# 103RCT6CORE.net
KiCad netlist of a schematic drawn in Altium Designer
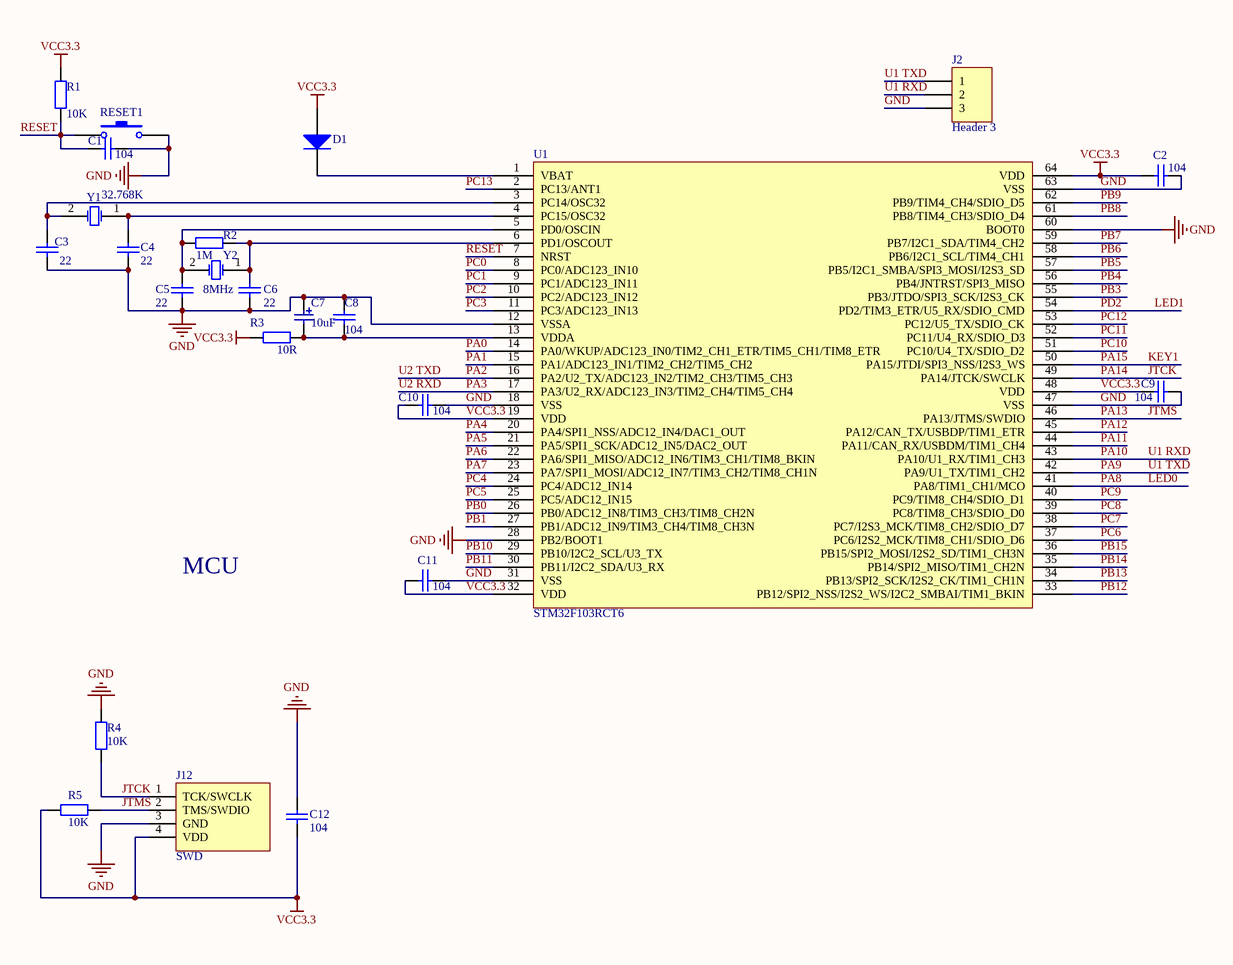
[diagram p0: 103RCT6CORE.SchDoc]

(export (version "E")
  (design (tool "Eeschema 10.0.6"))
  (components
    (comp (ref "C1")
      (value "104")
      (footprint "0805C")
      (description "Capacitor")
      (fields (field (name "Comment") "Cap") (field (name "PUBLISHER") "Altium Limited"))
      (libsource (lib "Miscellaneous Devices") (part "Cap"))
    )
    (comp (ref "C2")
      (value "104")
      (footprint "0805C")
      (description "Capacitor")
      (fields (field (name "Comment") "Cap") (field (name "PUBLISHER") "Altium Limited"))
      (libsource (lib "Miscellaneous Devices") (part "Cap"))
    )
    (comp (ref "C3")
      (value "22")
      (footprint "0805C")
      (description "Capacitor")
      (fields (field (name "Comment") "Cap") (field (name "PUBLISHER") "Altium Limited"))
      (libsource (lib "Miscellaneous Devices") (part "Cap"))
    )
    (comp (ref "C4")
      (value "22")
      (footprint "0805C")
      (description "Capacitor")
      (fields (field (name "Comment") "Cap") (field (name "PUBLISHER") "Altium Limited"))
      (libsource (lib "Miscellaneous Devices") (part "Cap"))
    )
    (comp (ref "C5")
      (value "22")
      (footprint "0805C")
      (description "Capacitor")
      (fields (field (name "Comment") "Cap") (field (name "PUBLISHER") "Altium Limited"))
      (libsource (lib "Miscellaneous Devices") (part "Cap"))
    )
    (comp (ref "C6")
      (value "22")
      (footprint "0805C")
      (description "Capacitor")
      (fields (field (name "Comment") "Cap") (field (name "PUBLISHER") "Altium Limited"))
      (libsource (lib "Miscellaneous Devices") (part "Cap"))
    )
    (comp (ref "C7") (value "10uF") (footprint "3216T") (libsource (lib "basic") (part "CAP-POL1")))
    (comp (ref "C8")
      (value "104")
      (footprint "0805c")
      (description "Capacitor")
      (fields (field (name "Comment") "Cap") (field (name "PUBLISHER") "Altium Limited"))
      (libsource (lib "Miscellaneous Devices") (part "Cap"))
    )
    (comp (ref "C9")
      (value "104")
      (footprint "0805C")
      (description "Capacitor")
      (fields (field (name "Comment") "Cap") (field (name "PUBLISHER") "Altium Limited"))
      (libsource (lib "Miscellaneous Devices") (part "Cap"))
    )
    (comp (ref "C10")
      (value "104")
      (footprint "0805C")
      (description "Capacitor")
      (fields (field (name "Comment") "Cap") (field (name "PUBLISHER") "Altium Limited"))
      (libsource (lib "Miscellaneous Devices") (part "Cap"))
    )
    (comp (ref "C11")
      (value "104")
      (footprint "0805C")
      (description "Capacitor")
      (fields (field (name "Comment") "Cap") (field (name "PUBLISHER") "Altium Limited"))
      (libsource (lib "Miscellaneous Devices") (part "Cap"))
    )
    (comp (ref "C12")
      (value "104")
      (footprint "0805C")
      (description "Capacitor")
      (fields (field (name "Comment") "Cap") (field (name "PUBLISHER") "Altium Limited"))
      (libsource (lib "Miscellaneous Devices") (part "Cap"))
    )
    (comp (ref "D1")
      (value "Diode 1N914")
      (footprint "1206")
      (description "High Conductance Fast Diode")
      (fields (field (name "PUBLISHER") "Altium Limited"))
      (libsource (lib "Miscellaneous Devices") (part "Diode 1N914"))
    )
    (comp (ref "J2")
      (value "Header 3")
      (footprint "HDR1X3")
      (description "Header, 3-Pin")
      (fields (field (name "PUBLISHER") "Altium Limited"))
      (libsource (lib "Miscellaneous Connectors") (part "Header 3"))
    )
    (comp (ref "J12") (value "SWD") (footprint "SWD") (libsource (lib "STM32") (part "SWD")))
    (comp (ref "R1")
      (value "10K")
      (footprint "0805")
      (description "Resistor")
      (fields (field (name "Comment") "Res2") (field (name "PUBLISHER") "Altium Limited"))
      (libsource (lib "") (part "Res2_2"))
    )
    (comp (ref "R2")
      (value "1M")
      (footprint "0805")
      (description "Resistor")
      (fields (field (name "Comment") "Res2") (field (name "PUBLISHER") "Altium Limited"))
      (libsource (lib "Miscellaneous Devices") (part "Res2"))
    )
    (comp (ref "R3")
      (value "10R")
      (footprint "0805")
      (description "Resistor")
      (fields (field (name "Comment") "Res2") (field (name "PUBLISHER") "Altium Limited"))
      (libsource (lib "Miscellaneous Devices") (part "Res2"))
    )
    (comp (ref "R4")
      (value "10K")
      (footprint "0805")
      (description "Resistor")
      (fields (field (name "Comment") "Res2") (field (name "PUBLISHER") "Altium Limited"))
      (libsource (lib "") (part "Res2_1"))
    )
    (comp (ref "R5")
      (value "10K")
      (footprint "0805")
      (description "Resistor")
      (fields (field (name "Comment") "Res2") (field (name "PUBLISHER") "Altium Limited"))
      (libsource (lib "Miscellaneous Devices") (part "Res2"))
    )
    (comp (ref "RESET1")
      (value "SW-PB")
      (footprint "SWITCH")
      (description "Switch")
      (fields (field (name "PUBLISHER") "Altium Limited"))
      (libsource (lib "Miscellaneous Devices") (part "SW-PB"))
    )
    (comp (ref "U1")
      (value "STM32F103RCT6")
      (footprint "STM32F103RCT6")
      (libsource (lib "Schlib1") (part "STM32F103RCT6"))
    )
    (comp (ref "Y1")
      (value "XTAL")
      (footprint "tc-26")
      (description "Crystal Oscillator")
      (fields (field (name "PUBLISHER") "Altium Limited"))
      (libsource (lib "Miscellaneous Devices") (part "XTAL"))
    )
    (comp (ref "Y2")
      (value "8MHz")
      (footprint "Y2")
      (description "Crystal Oscillator")
      (fields (field (name "PUBLISHER") "Altium Limited"))
      (libsource (lib "Miscellaneous Devices") (part "XTAL"))
    )
  )
  (nets
    (net (code "1") (name "/32.768K") (class "Default")
      (node (ref "C3") (pin "2") (pinfunction "2_2") (pintype "passive"))
      (node (ref "U1") (pin "3") (pinfunction "PC14/OSC32_3") (pintype "passive"))
      (node (ref "Y1") (pin "2") (pinfunction "OSC2_2") (pintype "passive"))
    )
    (net (code "2") (name "/JTCK") (class "Default")
      (node (ref "J12") (pin "1") (pinfunction "TCK/SWCLK_1") (pintype "passive"))
      (node (ref "R4") (pin "2") (pinfunction "2_2") (pintype "passive"))
      (node (ref "U1") (pin "49") (pinfunction "PA14/JTCK/SWCLK_49") (pintype "passive"))
    )
    (net (code "3") (name "/JTMS") (class "Default")
      (node (ref "J12") (pin "2") (pinfunction "TMS/SWDIO_2") (pintype "passive"))
      (node (ref "R5") (pin "1") (pinfunction "1_1") (pintype "passive"))
      (node (ref "U1") (pin "46") (pinfunction "PA13/JTMS/SWDIO_46") (pintype "passive"))
    )
    (net (code "4") (name "/KEY1") (class "Default")
      (node (ref "U1") (pin "50") (pinfunction "PA15/JTDI/SPI3_NSS/I2S3_WS_50") (pintype "passive"))
    )
    (net (code "5") (name "/LED0") (class "Default")
      (node (ref "U1") (pin "41") (pinfunction "PA8/TIM1_CH1/MCO_41") (pintype "passive"))
    )
    (net (code "6") (name "/LED1") (class "Default")
      (node (ref "U1") (pin "54") (pinfunction "PD2/TIM3_ETR/U5_RX/SDIO_CMD_54") (pintype "passive"))
    )
    (net (code "8") (name "/PA0") (class "Default")
      (node (ref "U1") (pin "14") (pinfunction "PA0/WKUP/ADC123_IN0/TIM2_CH1_ETR/TIM5_CH1/TIM8_ETR_14") (pintype "passive"))
    )
    (net (code "9") (name "/PA1") (class "Default")
      (node (ref "U1") (pin "15") (pinfunction "PA1/ADC123_IN1/TIM2_CH2/TIM5_CH2_15") (pintype "passive"))
    )
    (net (code "10") (name "/PA2") (class "Default")
      (node (ref "U1") (pin "16") (pinfunction "PA2/U2_TX/ADC123_IN2/TIM2_CH3/TIM5_CH3_16") (pintype "passive"))
    )
    (net (code "11") (name "/PA3") (class "Default")
      (node (ref "U1") (pin "17") (pinfunction "PA3/U2_RX/ADC123_IN3/TIM2_CH4/TIM5_CH4_17") (pintype "passive"))
    )
    (net (code "12") (name "/PA4") (class "Default")
      (node (ref "U1") (pin "20") (pinfunction "PA4/SPI1_NSS/ADC12_IN4/DAC1_OUT_20") (pintype "passive"))
    )
    (net (code "13") (name "/PA5") (class "Default")
      (node (ref "U1") (pin "21") (pinfunction "PA5/SPI1_SCK/ADC12_IN5/DAC2_OUT_21") (pintype "passive"))
    )
    (net (code "14") (name "/PA6") (class "Default")
      (node (ref "U1") (pin "22") (pinfunction "PA6/SPI1_MISO/ADC12_IN6/TIM3_CH1/TIM8_BKIN_22") (pintype "passive"))
    )
    (net (code "15") (name "/PA7") (class "Default")
      (node (ref "U1") (pin "23") (pinfunction "PA7/SPI1_MOSI/ADC12_IN7/TIM3_CH2/TIM8_CH1N_23") (pintype "passive"))
    )
    (net (code "16") (name "/PA9") (class "Default")
      (node (ref "J2") (pin "1") (pinfunction "1_1") (pintype "passive"))
      (node (ref "U1") (pin "42") (pinfunction "PA9/U1_TX/TIM1_CH2_42") (pintype "passive"))
    )
    (net (code "17") (name "/PA10") (class "Default")
      (node (ref "J2") (pin "2") (pinfunction "2_2") (pintype "passive"))
      (node (ref "U1") (pin "43") (pinfunction "PA10/U1_RX/TIM1_CH3_43") (pintype "passive"))
    )
    (net (code "18") (name "/PA11") (class "Default")
      (node (ref "U1") (pin "44") (pinfunction "PA11/CAN_RX/USBDM/TIM1_CH4_44") (pintype "passive"))
    )
    (net (code "19") (name "/PA12") (class "Default")
      (node (ref "U1") (pin "45") (pinfunction "PA12/CAN_TX/USBDP/TIM1_ETR_45") (pintype "passive"))
    )
    (net (code "20") (name "/PB0") (class "Default")
      (node (ref "U1") (pin "26") (pinfunction "PB0/ADC12_IN8/TIM3_CH3/TIM8_CH2N_26") (pintype "passive"))
    )
    (net (code "21") (name "/PB1") (class "Default")
      (node (ref "U1") (pin "27") (pinfunction "PB1/ADC12_IN9/TIM3_CH4/TIM8_CH3N_27") (pintype "passive"))
    )
    (net (code "22") (name "/PB3") (class "Default")
      (node (ref "U1") (pin "55") (pinfunction "PB3/JTDO/SPI3_SCK/I2S3_CK_55") (pintype "passive"))
    )
    (net (code "23") (name "/PB4") (class "Default")
      (node (ref "U1") (pin "56") (pinfunction "PB4/JNTRST/SPI3_MISO_56") (pintype "passive"))
    )
    (net (code "24") (name "/PB5") (class "Default")
      (node (ref "U1") (pin "57") (pinfunction "PB5/I2C1_SMBA/SPI3_MOSI/I2S3_SD_57") (pintype "passive"))
    )
    (net (code "25") (name "/PB6") (class "Default")
      (node (ref "U1") (pin "58") (pinfunction "PB6/I2C1_SCL/TIM4_CH1_58") (pintype "passive"))
    )
    (net (code "26") (name "/PB7") (class "Default")
      (node (ref "U1") (pin "59") (pinfunction "PB7/I2C1_SDA/TIM4_CH2_59") (pintype "passive"))
    )
    (net (code "27") (name "/PB8") (class "Default")
      (node (ref "U1") (pin "61") (pinfunction "PB8/TIM4_CH3/SDIO_D4_61") (pintype "passive"))
    )
    (net (code "28") (name "/PB9") (class "Default")
      (node (ref "U1") (pin "62") (pinfunction "PB9/TIM4_CH4/SDIO_D5_62") (pintype "passive"))
    )
    (net (code "29") (name "/PB10") (class "Default")
      (node (ref "U1") (pin "29") (pinfunction "PB10/I2C2_SCL/U3_TX_29") (pintype "passive"))
    )
    (net (code "30") (name "/PB11") (class "Default")
      (node (ref "U1") (pin "30") (pinfunction "PB11/I2C2_SDA/U3_RX_30") (pintype "passive"))
    )
    (net (code "31") (name "/PB12") (class "Default")
      (node (ref "U1") (pin "33") (pinfunction "PB12/SPI2_NSS/I2S2_WS/I2C2_SMBAI/TIM1_BKIN_33") (pintype "passive"))
    )
    (net (code "32") (name "/PB13") (class "Default")
      (node (ref "U1") (pin "34") (pinfunction "PB13/SPI2_SCK/I2S2_CK/TIM1_CH1N_34") (pintype "passive"))
    )
    (net (code "33") (name "/PB14") (class "Default")
      (node (ref "U1") (pin "35") (pinfunction "PB14/SPI2_MISO/TIM1_CH2N_35") (pintype "passive"))
    )
    (net (code "34") (name "/PB15") (class "Default")
      (node (ref "U1") (pin "36") (pinfunction "PB15/SPI2_MOSI/I2S2_SD/TIM1_CH3N_36") (pintype "passive"))
    )
    (net (code "35") (name "/PC0") (class "Default")
      (node (ref "U1") (pin "8") (pinfunction "PC0/ADC123_IN10_8") (pintype "passive"))
    )
    (net (code "36") (name "/PC1") (class "Default")
      (node (ref "U1") (pin "9") (pinfunction "PC1/ADC123_IN11_9") (pintype "passive"))
    )
    (net (code "37") (name "/PC2") (class "Default")
      (node (ref "U1") (pin "10") (pinfunction "PC2/ADC123_IN12_10") (pintype "passive"))
    )
    (net (code "38") (name "/PC3") (class "Default")
      (node (ref "U1") (pin "11") (pinfunction "PC3/ADC123_IN13_11") (pintype "passive"))
    )
    (net (code "39") (name "/PC4") (class "Default")
      (node (ref "U1") (pin "24") (pinfunction "PC4/ADC12_IN14_24") (pintype "passive"))
    )
    (net (code "40") (name "/PC5") (class "Default")
      (node (ref "U1") (pin "25") (pinfunction "PC5/ADC12_IN15_25") (pintype "passive"))
    )
    (net (code "41") (name "/PC6") (class "Default")
      (node (ref "U1") (pin "37") (pinfunction "PC6/I2S2_MCK/TIM8_CH1/SDIO_D6_37") (pintype "passive"))
    )
    (net (code "42") (name "/PC7") (class "Default")
      (node (ref "U1") (pin "38") (pinfunction "PC7/I2S3_MCK/TIM8_CH2/SDIO_D7_38") (pintype "passive"))
    )
    (net (code "43") (name "/PC8") (class "Default")
      (node (ref "U1") (pin "39") (pinfunction "PC8/TIM8_CH3/SDIO_D0_39") (pintype "passive"))
    )
    (net (code "44") (name "/PC9") (class "Default")
      (node (ref "U1") (pin "40") (pinfunction "PC9/TIM8_CH4/SDIO_D1_40") (pintype "passive"))
    )
    (net (code "45") (name "/PC10") (class "Default")
      (node (ref "U1") (pin "51") (pinfunction "PC10/U4_TX/SDIO_D2_51") (pintype "passive"))
    )
    (net (code "46") (name "/PC11") (class "Default")
      (node (ref "U1") (pin "52") (pinfunction "PC11/U4_RX/SDIO_D3_52") (pintype "passive"))
    )
    (net (code "47") (name "/PC12") (class "Default")
      (node (ref "U1") (pin "53") (pinfunction "PC12/U5_TX/SDIO_CK_53") (pintype "passive"))
    )
    (net (code "48") (name "/PC13") (class "Default")
      (node (ref "U1") (pin "2") (pinfunction "PC13/ANT1_2") (pintype "passive"))
    )
    (net (code "49") (name "/RESET") (class "Default")
      (node (ref "C1") (pin "1") (pinfunction "1_1") (pintype "passive"))
      (node (ref "R1") (pin "1") (pinfunction "1_1") (pintype "passive"))
      (node (ref "RESET1") (pin "1") (pinfunction "1_1") (pintype "passive"))
      (node (ref "U1") (pin "7") (pinfunction "NRST_7") (pintype "passive"))
    )
    (net (code "50") (name "GND") (class "Default")
      (node (ref "C1") (pin "2") (pinfunction "2_2") (pintype "passive"))
      (node (ref "C10") (pin "1") (pinfunction "1_1") (pintype "passive"))
      (node (ref "C11") (pin "2") (pinfunction "2_2") (pintype "passive"))
      (node (ref "C12") (pin "1") (pinfunction "1_1") (pintype "passive"))
      (node (ref "C2") (pin "2") (pinfunction "2_2") (pintype "passive"))
      (node (ref "C3") (pin "1") (pinfunction "1_1") (pintype "passive"))
      (node (ref "C4") (pin "1") (pinfunction "1_1") (pintype "passive"))
      (node (ref "C5") (pin "1") (pinfunction "1_1") (pintype "passive"))
      (node (ref "C6") (pin "2") (pinfunction "2_2") (pintype "passive"))
      (node (ref "C7") (pin "1") (pinfunction "1_1") (pintype "passive"))
      (node (ref "C8") (pin "2") (pinfunction "2_2") (pintype "passive"))
      (node (ref "C9") (pin "2") (pinfunction "2_2") (pintype "passive"))
      (node (ref "J12") (pin "3") (pinfunction "GND_3") (pintype "passive"))
      (node (ref "J2") (pin "3") (pinfunction "3_3") (pintype "passive"))
      (node (ref "R4") (pin "1") (pinfunction "1_1") (pintype "passive"))
      (node (ref "RESET1") (pin "2") (pinfunction "2_2") (pintype "passive"))
      (node (ref "U1") (pin "12") (pinfunction "VSSA_12") (pintype "passive"))
      (node (ref "U1") (pin "18") (pinfunction "VSS_18") (pintype "passive"))
      (node (ref "U1") (pin "28") (pinfunction "PB2/BOOT1_28") (pintype "passive"))
      (node (ref "U1") (pin "31") (pinfunction "VSS_31") (pintype "passive"))
      (node (ref "U1") (pin "47") (pinfunction "VSS_47") (pintype "passive"))
      (node (ref "U1") (pin "60") (pinfunction "BOOT0_60") (pintype "passive"))
      (node (ref "U1") (pin "63") (pinfunction "VSS_63") (pintype "passive"))
    )
    (net (code "51") (name "Net-(D1-K)") (class "Default")
      (node (ref "D1") (pin "2") (pinfunction "K_2") (pintype "passive"))
      (node (ref "U1") (pin "1") (pinfunction "VBAT_1") (pintype "passive"))
    )
    (net (code "52") (name "Net-(U1-PC15{slash}OSC32)") (class "Default")
      (node (ref "C4") (pin "2") (pinfunction "2_2") (pintype "passive"))
      (node (ref "U1") (pin "4") (pinfunction "PC15/OSC32_4") (pintype "passive"))
      (node (ref "Y1") (pin "1") (pinfunction "OSC1_1") (pintype "passive"))
    )
    (net (code "53") (name "Net-(U1-PD0{slash}OSCIN)") (class "Default")
      (node (ref "C5") (pin "2") (pinfunction "2_2") (pintype "passive"))
      (node (ref "R2") (pin "2") (pinfunction "2_2") (pintype "passive"))
      (node (ref "U1") (pin "5") (pinfunction "PD0/OSCIN_5") (pintype "passive"))
      (node (ref "Y2") (pin "2") (pinfunction "OSC2_2") (pintype "passive"))
    )
    (net (code "54") (name "Net-(U1-PD1{slash}OSCOUT)") (class "Default")
      (node (ref "C6") (pin "1") (pinfunction "1_1") (pintype "passive"))
      (node (ref "R2") (pin "1") (pinfunction "1_1") (pintype "passive"))
      (node (ref "U1") (pin "6") (pinfunction "PD1/OSCOUT_6") (pintype "passive"))
      (node (ref "Y2") (pin "1") (pinfunction "OSC1_1") (pintype "passive"))
    )
    (net (code "55") (name "Net-(U1-VDDA)") (class "Default")
      (node (ref "C7") (pin "2") (pinfunction "2_2") (pintype "passive"))
      (node (ref "C8") (pin "1") (pinfunction "1_1") (pintype "passive"))
      (node (ref "R3") (pin "1") (pinfunction "1_1") (pintype "passive"))
      (node (ref "U1") (pin "13") (pinfunction "VDDA_13") (pintype "passive"))
    )
    (net (code "56") (name "VCC3.3") (class "Default")
      (node (ref "C10") (pin "2") (pinfunction "2_2") (pintype "passive"))
      (node (ref "C11") (pin "1") (pinfunction "1_1") (pintype "passive"))
      (node (ref "C12") (pin "2") (pinfunction "2_2") (pintype "passive"))
      (node (ref "C2") (pin "1") (pinfunction "1_1") (pintype "passive"))
      (node (ref "C9") (pin "1") (pinfunction "1_1") (pintype "passive"))
      (node (ref "D1") (pin "1") (pinfunction "A_1") (pintype "passive"))
      (node (ref "J12") (pin "4") (pinfunction "VDD_4") (pintype "passive"))
      (node (ref "R1") (pin "2") (pinfunction "2_2") (pintype "passive"))
      (node (ref "R3") (pin "2") (pinfunction "2_2") (pintype "passive"))
      (node (ref "R5") (pin "2") (pinfunction "2_2") (pintype "passive"))
      (node (ref "U1") (pin "19") (pinfunction "VDD_19") (pintype "passive"))
      (node (ref "U1") (pin "32") (pinfunction "VDD_32") (pintype "passive"))
      (node (ref "U1") (pin "48") (pinfunction "VDD_48") (pintype "passive"))
      (node (ref "U1") (pin "64") (pinfunction "VDD_64") (pintype "passive"))
    )
  )
)
